# tricorder-photodiode-breakout-mk-1_0.net
KiCad netlist of a schematic drawn in EAGLE
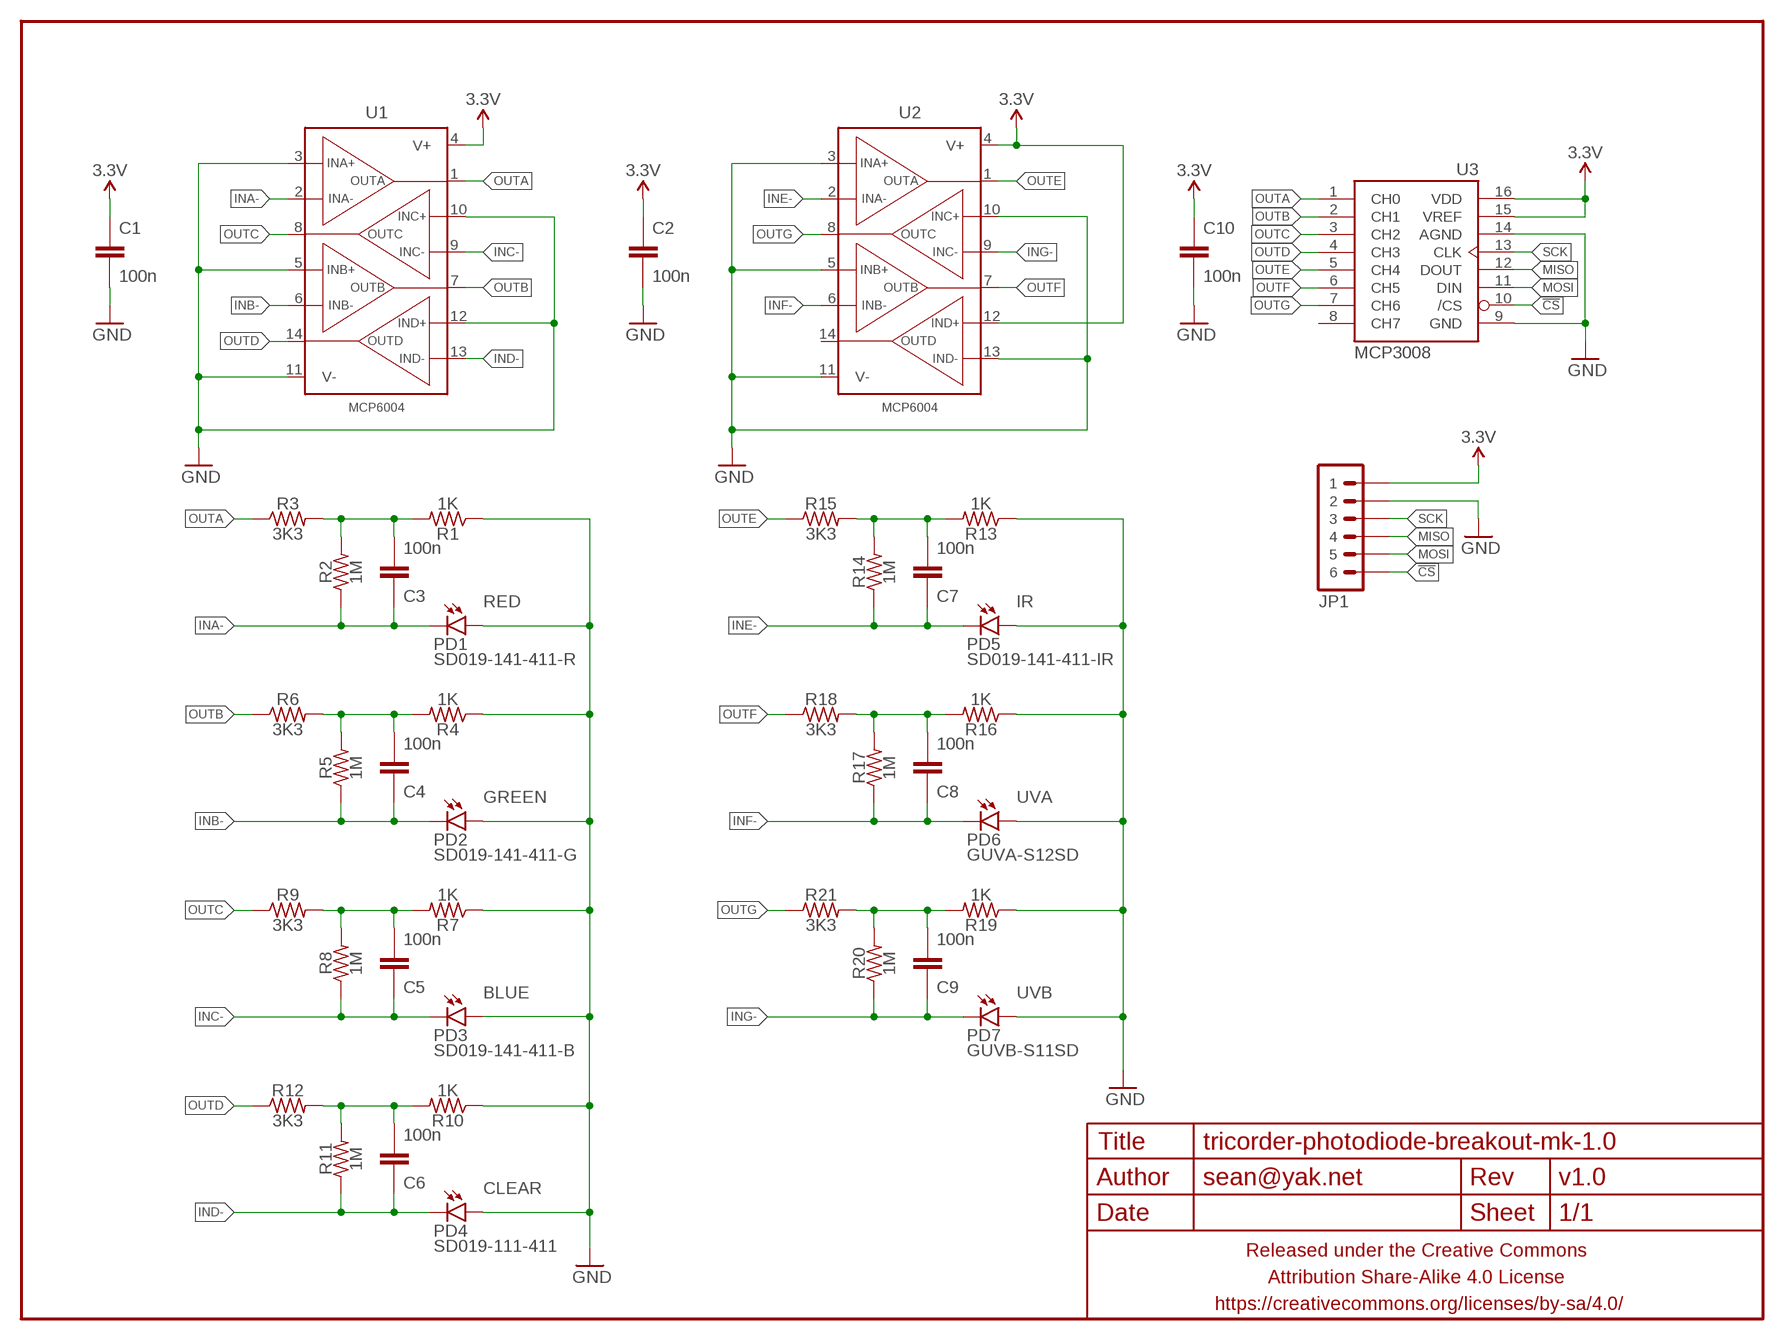
[diagram p0: schematic, sheet 1]

(export (version "E")
  (design (tool "Eeschema 10.0.6"))
  (components
    (comp (ref "C1")
      (value "100n")
      (footprint "eagle-import:C0603")
      (libsource (lib "eagle-import") (part "CAPACITOR-CERAMICC0603"))
    )
    (comp (ref "C2")
      (value "100n")
      (footprint "eagle-import:C0603")
      (libsource (lib "eagle-import") (part "CAPACITOR-CERAMICC0603"))
    )
    (comp (ref "C3")
      (value "100n")
      (footprint "eagle-import:C0603")
      (libsource (lib "eagle-import") (part "CAPACITOR-CERAMICC0603"))
    )
    (comp (ref "C4")
      (value "100n")
      (footprint "eagle-import:C0603")
      (libsource (lib "eagle-import") (part "CAPACITOR-CERAMICC0603"))
    )
    (comp (ref "C5")
      (value "100n")
      (footprint "eagle-import:C0603")
      (libsource (lib "eagle-import") (part "CAPACITOR-CERAMICC0603"))
    )
    (comp (ref "C6")
      (value "100n")
      (footprint "eagle-import:C0603")
      (libsource (lib "eagle-import") (part "CAPACITOR-CERAMICC0603"))
    )
    (comp (ref "C7")
      (value "100n")
      (footprint "eagle-import:C0603")
      (libsource (lib "eagle-import") (part "CAPACITOR-CERAMICC0603"))
    )
    (comp (ref "C8")
      (value "100n")
      (footprint "eagle-import:C0603")
      (libsource (lib "eagle-import") (part "CAPACITOR-CERAMICC0603"))
    )
    (comp (ref "C9")
      (value "100n")
      (footprint "eagle-import:C0603")
      (libsource (lib "eagle-import") (part "CAPACITOR-CERAMICC0603"))
    )
    (comp (ref "C10")
      (value "100n")
      (footprint "eagle-import:C0603")
      (libsource (lib "eagle-import") (part "CAPACITOR-CERAMICC0603"))
    )
    (comp (ref "FRAME1")
      (value "FRAME-LETTERNO_PACKAGE")
      (footprint "eagle-import:DUMMY")
      (fields (field (name "DESIGNER") "sean@yak.net") (field (name "VERSION") "v1.0"))
      (libsource (lib "eagle-import") (part "FRAME-LETTERNO_PACKAGE"))
    )
    (comp (ref "JP1")
      (value "M06JST-PH-PTH-VERT")
      (footprint "eagle-import:JST-6-PH-VERT-PTH")
      (libsource (lib "eagle-import") (part "M06JST-PH-PTH-VERT"))
    )
    (comp (ref "PD1")
      (value "SD019-141-411-R")
      (footprint "eagle-import:LED-0805")
      (libsource (lib "eagle-import") (part "PHOTODIODESMD-0805"))
    )
    (comp (ref "PD2")
      (value "SD019-141-411-G")
      (footprint "eagle-import:LED-0805")
      (libsource (lib "eagle-import") (part "PHOTODIODESMD-0805"))
    )
    (comp (ref "PD3")
      (value "SD019-141-411-B")
      (footprint "eagle-import:LED-0805")
      (libsource (lib "eagle-import") (part "PHOTODIODESMD-0805"))
    )
    (comp (ref "PD4")
      (value "SD019-111-411")
      (footprint "eagle-import:LED-0805")
      (libsource (lib "eagle-import") (part "PHOTODIODESMD-0805"))
    )
    (comp (ref "PD5")
      (value "SD019-141-411-IR")
      (footprint "eagle-import:LED-0805")
      (libsource (lib "eagle-import") (part "PHOTODIODESMD-0805"))
    )
    (comp (ref "PD6")
      (value "GUVA-S12SD")
      (footprint "eagle-import:LED3528")
      (libsource (lib "eagle-import") (part "PHOTODIODESMD-3528"))
    )
    (comp (ref "PD7")
      (value "GUVB-S11SD")
      (footprint "eagle-import:LED3528")
      (libsource (lib "eagle-import") (part "PHOTODIODESMD-3528"))
    )
    (comp (ref "R1")
      (value "1K")
      (footprint "eagle-import:R0603")
      (libsource (lib "eagle-import") (part "RESISTORR0603"))
    )
    (comp (ref "R2")
      (value "1M")
      (footprint "eagle-import:R0603")
      (libsource (lib "eagle-import") (part "RESISTORR0603"))
    )
    (comp (ref "R3")
      (value "3K3")
      (footprint "eagle-import:R0603")
      (libsource (lib "eagle-import") (part "RESISTORR0603"))
    )
    (comp (ref "R4")
      (value "1K")
      (footprint "eagle-import:R0603")
      (libsource (lib "eagle-import") (part "RESISTORR0603"))
    )
    (comp (ref "R5")
      (value "1M")
      (footprint "eagle-import:R0603")
      (libsource (lib "eagle-import") (part "RESISTORR0603"))
    )
    (comp (ref "R6")
      (value "3K3")
      (footprint "eagle-import:R0603")
      (libsource (lib "eagle-import") (part "RESISTORR0603"))
    )
    (comp (ref "R7")
      (value "1K")
      (footprint "eagle-import:R0603")
      (libsource (lib "eagle-import") (part "RESISTORR0603"))
    )
    (comp (ref "R8")
      (value "1M")
      (footprint "eagle-import:R0603")
      (libsource (lib "eagle-import") (part "RESISTORR0603"))
    )
    (comp (ref "R9")
      (value "3K3")
      (footprint "eagle-import:R0603")
      (libsource (lib "eagle-import") (part "RESISTORR0603"))
    )
    (comp (ref "R10")
      (value "1K")
      (footprint "eagle-import:R0603")
      (libsource (lib "eagle-import") (part "RESISTORR0603"))
    )
    (comp (ref "R11")
      (value "1M")
      (footprint "eagle-import:R0603")
      (libsource (lib "eagle-import") (part "RESISTORR0603"))
    )
    (comp (ref "R12")
      (value "3K3")
      (footprint "eagle-import:R0603")
      (libsource (lib "eagle-import") (part "RESISTORR0603"))
    )
    (comp (ref "R13")
      (value "1K")
      (footprint "eagle-import:R0603")
      (libsource (lib "eagle-import") (part "RESISTORR0603"))
    )
    (comp (ref "R14")
      (value "1M")
      (footprint "eagle-import:R0603")
      (libsource (lib "eagle-import") (part "RESISTORR0603"))
    )
    (comp (ref "R15")
      (value "3K3")
      (footprint "eagle-import:R0603")
      (libsource (lib "eagle-import") (part "RESISTORR0603"))
    )
    (comp (ref "R16")
      (value "1K")
      (footprint "eagle-import:R0603")
      (libsource (lib "eagle-import") (part "RESISTORR0603"))
    )
    (comp (ref "R17")
      (value "1M")
      (footprint "eagle-import:R0603")
      (libsource (lib "eagle-import") (part "RESISTORR0603"))
    )
    (comp (ref "R18")
      (value "3K3")
      (footprint "eagle-import:R0603")
      (libsource (lib "eagle-import") (part "RESISTORR0603"))
    )
    (comp (ref "R19")
      (value "1K")
      (footprint "eagle-import:R0603")
      (libsource (lib "eagle-import") (part "RESISTORR0603"))
    )
    (comp (ref "R20")
      (value "1M")
      (footprint "eagle-import:R0603")
      (libsource (lib "eagle-import") (part "RESISTORR0603"))
    )
    (comp (ref "R21")
      (value "3K3")
      (footprint "eagle-import:R0603")
      (libsource (lib "eagle-import") (part "RESISTORR0603"))
    )
    (comp (ref "U1")
      (value "MCP6004")
      (footprint "eagle-import:SO14")
      (libsource (lib "eagle-import") (part "MCP6004SOIC14"))
    )
    (comp (ref "U2")
      (value "MCP6004")
      (footprint "eagle-import:SO14")
      (libsource (lib "eagle-import") (part "MCP6004SOIC14"))
    )
    (comp (ref "U3")
      (value "MCP3008")
      (footprint "eagle-import:SO16")
      (libsource (lib "eagle-import") (part "MCP3008SOIC16"))
    )
  )
  (nets
    (net (code "1") (name "/~{CS}") (class "Default")
      (node (ref "JP1") (pin "6") (pinfunction "6_6") (pintype "passive"))
      (node (ref "U3") (pin "10") (pinfunction "/CS_10") (pintype "input"))
    )
    (net (code "2") (name "3.3V") (class "Default")
      (node (ref "C1") (pin "1") (pinfunction "1_1") (pintype "passive"))
      (node (ref "C10") (pin "1") (pinfunction "1_1") (pintype "passive"))
      (node (ref "C2") (pin "1") (pinfunction "1_1") (pintype "passive"))
      (node (ref "JP1") (pin "1") (pinfunction "1_1") (pintype "passive"))
      (node (ref "U1") (pin "4") (pinfunction "V+_4") (pintype "power_in"))
      (node (ref "U2") (pin "12") (pinfunction "IND+_12") (pintype "input"))
      (node (ref "U2") (pin "4") (pinfunction "V+_4") (pintype "power_in"))
      (node (ref "U3") (pin "15") (pinfunction "VREF_15") (pintype "input"))
      (node (ref "U3") (pin "16") (pinfunction "VDD_16") (pintype "power_in"))
    )
    (net (code "3") (name "GND") (class "Default")
      (node (ref "C1") (pin "2") (pinfunction "2_2") (pintype "passive"))
      (node (ref "C10") (pin "2") (pinfunction "2_2") (pintype "passive"))
      (node (ref "C2") (pin "2") (pinfunction "2_2") (pintype "passive"))
      (node (ref "JP1") (pin "2") (pinfunction "2_2") (pintype "passive"))
      (node (ref "PD1") (pin "A") (pinfunction "A_A") (pintype "passive"))
      (node (ref "PD2") (pin "A") (pinfunction "A_A") (pintype "passive"))
      (node (ref "PD3") (pin "A") (pinfunction "A_A") (pintype "passive"))
      (node (ref "PD4") (pin "A") (pinfunction "A_A") (pintype "passive"))
      (node (ref "PD5") (pin "A") (pinfunction "A_A") (pintype "passive"))
      (node (ref "PD6") (pin "A") (pinfunction "A_A") (pintype "passive"))
      (node (ref "PD7") (pin "A") (pinfunction "A_A") (pintype "passive"))
      (node (ref "R1") (pin "1") (pinfunction "1_1") (pintype "passive"))
      (node (ref "R10") (pin "1") (pinfunction "1_1") (pintype "passive"))
      (node (ref "R13") (pin "1") (pinfunction "1_1") (pintype "passive"))
      (node (ref "R16") (pin "1") (pinfunction "1_1") (pintype "passive"))
      (node (ref "R19") (pin "1") (pinfunction "1_1") (pintype "passive"))
      (node (ref "R4") (pin "1") (pinfunction "1_1") (pintype "passive"))
      (node (ref "R7") (pin "1") (pinfunction "1_1") (pintype "passive"))
      (node (ref "U1") (pin "10") (pinfunction "INC+_10") (pintype "input"))
      (node (ref "U1") (pin "11") (pinfunction "V-_11") (pintype "power_in"))
      (node (ref "U1") (pin "12") (pinfunction "IND+_12") (pintype "input"))
      (node (ref "U1") (pin "3") (pinfunction "INA+_3") (pintype "input"))
      (node (ref "U1") (pin "5") (pinfunction "INB+_5") (pintype "input"))
      (node (ref "U2") (pin "10") (pinfunction "INC+_10") (pintype "input"))
      (node (ref "U2") (pin "11") (pinfunction "V-_11") (pintype "power_in"))
      (node (ref "U2") (pin "13") (pinfunction "IND-_13") (pintype "input"))
      (node (ref "U2") (pin "3") (pinfunction "INA+_3") (pintype "input"))
      (node (ref "U2") (pin "5") (pinfunction "INB+_5") (pintype "input"))
      (node (ref "U3") (pin "14") (pinfunction "AGND_14") (pintype "power_in"))
      (node (ref "U3") (pin "9") (pinfunction "GND_9") (pintype "power_in"))
    )
    (net (code "4") (name "INA-") (class "Default")
      (node (ref "C3") (pin "1") (pinfunction "1_1") (pintype "passive"))
      (node (ref "PD1") (pin "C") (pinfunction "C_C") (pintype "passive"))
      (node (ref "R2") (pin "1") (pinfunction "1_1") (pintype "passive"))
      (node (ref "U1") (pin "2") (pinfunction "INA-_2") (pintype "input"))
    )
    (net (code "5") (name "INB-") (class "Default")
      (node (ref "C4") (pin "1") (pinfunction "1_1") (pintype "passive"))
      (node (ref "PD2") (pin "C") (pinfunction "C_C") (pintype "passive"))
      (node (ref "R5") (pin "1") (pinfunction "1_1") (pintype "passive"))
      (node (ref "U1") (pin "6") (pinfunction "INB-_6") (pintype "input"))
    )
    (net (code "6") (name "INC-") (class "Default")
      (node (ref "C5") (pin "1") (pinfunction "1_1") (pintype "passive"))
      (node (ref "PD3") (pin "C") (pinfunction "C_C") (pintype "passive"))
      (node (ref "R8") (pin "1") (pinfunction "1_1") (pintype "passive"))
      (node (ref "U1") (pin "9") (pinfunction "INC-_9") (pintype "input"))
    )
    (net (code "7") (name "IND-") (class "Default")
      (node (ref "C6") (pin "1") (pinfunction "1_1") (pintype "passive"))
      (node (ref "PD4") (pin "C") (pinfunction "C_C") (pintype "passive"))
      (node (ref "R11") (pin "1") (pinfunction "1_1") (pintype "passive"))
      (node (ref "U1") (pin "13") (pinfunction "IND-_13") (pintype "input"))
    )
    (net (code "8") (name "INE-") (class "Default")
      (node (ref "C7") (pin "1") (pinfunction "1_1") (pintype "passive"))
      (node (ref "PD5") (pin "C") (pinfunction "C_C") (pintype "passive"))
      (node (ref "R14") (pin "1") (pinfunction "1_1") (pintype "passive"))
      (node (ref "U2") (pin "2") (pinfunction "INA-_2") (pintype "input"))
    )
    (net (code "9") (name "INF-") (class "Default")
      (node (ref "C8") (pin "1") (pinfunction "1_1") (pintype "passive"))
      (node (ref "PD6") (pin "K") (pinfunction "C_K") (pintype "passive"))
      (node (ref "R17") (pin "1") (pinfunction "1_1") (pintype "passive"))
      (node (ref "U2") (pin "6") (pinfunction "INB-_6") (pintype "input"))
    )
    (net (code "10") (name "ING-") (class "Default")
      (node (ref "C9") (pin "1") (pinfunction "1_1") (pintype "passive"))
      (node (ref "PD7") (pin "K") (pinfunction "C_K") (pintype "passive"))
      (node (ref "R20") (pin "1") (pinfunction "1_1") (pintype "passive"))
      (node (ref "U2") (pin "9") (pinfunction "INC-_9") (pintype "input"))
    )
    (net (code "11") (name "MISO") (class "Default")
      (node (ref "JP1") (pin "4") (pinfunction "4_4") (pintype "passive"))
      (node (ref "U3") (pin "12") (pinfunction "DOUT_12") (pintype "output"))
    )
    (net (code "12") (name "MOSI") (class "Default")
      (node (ref "JP1") (pin "5") (pinfunction "5_5") (pintype "passive"))
      (node (ref "U3") (pin "11") (pinfunction "DIN_11") (pintype "input"))
    )
    (net (code "13") (name "Net-(C3-Pad2)") (class "Default")
      (node (ref "C3") (pin "2") (pinfunction "2_2") (pintype "passive"))
      (node (ref "R1") (pin "2") (pinfunction "2_2") (pintype "passive"))
      (node (ref "R2") (pin "2") (pinfunction "2_2") (pintype "passive"))
      (node (ref "R3") (pin "2") (pinfunction "2_2") (pintype "passive"))
    )
    (net (code "14") (name "Net-(C4-Pad2)") (class "Default")
      (node (ref "C4") (pin "2") (pinfunction "2_2") (pintype "passive"))
      (node (ref "R4") (pin "2") (pinfunction "2_2") (pintype "passive"))
      (node (ref "R5") (pin "2") (pinfunction "2_2") (pintype "passive"))
      (node (ref "R6") (pin "2") (pinfunction "2_2") (pintype "passive"))
    )
    (net (code "15") (name "Net-(C5-Pad2)") (class "Default")
      (node (ref "C5") (pin "2") (pinfunction "2_2") (pintype "passive"))
      (node (ref "R7") (pin "2") (pinfunction "2_2") (pintype "passive"))
      (node (ref "R8") (pin "2") (pinfunction "2_2") (pintype "passive"))
      (node (ref "R9") (pin "2") (pinfunction "2_2") (pintype "passive"))
    )
    (net (code "16") (name "Net-(C6-Pad2)") (class "Default")
      (node (ref "C6") (pin "2") (pinfunction "2_2") (pintype "passive"))
      (node (ref "R10") (pin "2") (pinfunction "2_2") (pintype "passive"))
      (node (ref "R11") (pin "2") (pinfunction "2_2") (pintype "passive"))
      (node (ref "R12") (pin "2") (pinfunction "2_2") (pintype "passive"))
    )
    (net (code "17") (name "Net-(C7-Pad2)") (class "Default")
      (node (ref "C7") (pin "2") (pinfunction "2_2") (pintype "passive"))
      (node (ref "R13") (pin "2") (pinfunction "2_2") (pintype "passive"))
      (node (ref "R14") (pin "2") (pinfunction "2_2") (pintype "passive"))
      (node (ref "R15") (pin "2") (pinfunction "2_2") (pintype "passive"))
    )
    (net (code "18") (name "Net-(C8-Pad2)") (class "Default")
      (node (ref "C8") (pin "2") (pinfunction "2_2") (pintype "passive"))
      (node (ref "R16") (pin "2") (pinfunction "2_2") (pintype "passive"))
      (node (ref "R17") (pin "2") (pinfunction "2_2") (pintype "passive"))
      (node (ref "R18") (pin "2") (pinfunction "2_2") (pintype "passive"))
    )
    (net (code "19") (name "Net-(C9-Pad2)") (class "Default")
      (node (ref "C9") (pin "2") (pinfunction "2_2") (pintype "passive"))
      (node (ref "R19") (pin "2") (pinfunction "2_2") (pintype "passive"))
      (node (ref "R20") (pin "2") (pinfunction "2_2") (pintype "passive"))
      (node (ref "R21") (pin "2") (pinfunction "2_2") (pintype "passive"))
    )
    (net (code "20") (name "OUTA") (class "Default")
      (node (ref "R3") (pin "1") (pinfunction "1_1") (pintype "passive"))
      (node (ref "U1") (pin "1") (pinfunction "OUTA_1") (pintype "output"))
      (node (ref "U3") (pin "1") (pinfunction "CH0_1") (pintype "input"))
    )
    (net (code "21") (name "OUTB") (class "Default")
      (node (ref "R6") (pin "1") (pinfunction "1_1") (pintype "passive"))
      (node (ref "U1") (pin "7") (pinfunction "OUTB_7") (pintype "output"))
      (node (ref "U3") (pin "2") (pinfunction "CH1_2") (pintype "input"))
    )
    (net (code "22") (name "OUTC") (class "Default")
      (node (ref "R9") (pin "1") (pinfunction "1_1") (pintype "passive"))
      (node (ref "U1") (pin "8") (pinfunction "OUTC_8") (pintype "output"))
      (node (ref "U3") (pin "3") (pinfunction "CH2_3") (pintype "input"))
    )
    (net (code "23") (name "OUTD") (class "Default")
      (node (ref "R12") (pin "1") (pinfunction "1_1") (pintype "passive"))
      (node (ref "U1") (pin "14") (pinfunction "OUTD_14") (pintype "output"))
      (node (ref "U3") (pin "4") (pinfunction "CH3_4") (pintype "input"))
    )
    (net (code "24") (name "OUTE") (class "Default")
      (node (ref "R15") (pin "1") (pinfunction "1_1") (pintype "passive"))
      (node (ref "U2") (pin "1") (pinfunction "OUTA_1") (pintype "output"))
      (node (ref "U3") (pin "5") (pinfunction "CH4_5") (pintype "input"))
    )
    (net (code "25") (name "OUTF") (class "Default")
      (node (ref "R18") (pin "1") (pinfunction "1_1") (pintype "passive"))
      (node (ref "U2") (pin "7") (pinfunction "OUTB_7") (pintype "output"))
      (node (ref "U3") (pin "6") (pinfunction "CH5_6") (pintype "input"))
    )
    (net (code "26") (name "OUTG") (class "Default")
      (node (ref "R21") (pin "1") (pinfunction "1_1") (pintype "passive"))
      (node (ref "U2") (pin "8") (pinfunction "OUTC_8") (pintype "output"))
      (node (ref "U3") (pin "7") (pinfunction "CH6_7") (pintype "input"))
    )
    (net (code "27") (name "SCK") (class "Default")
      (node (ref "JP1") (pin "3") (pinfunction "3_3") (pintype "passive"))
      (node (ref "U3") (pin "13") (pinfunction "CLK_13") (pintype "input"))
    )
    (net (code "28") (name "unconnected-(U2-OUTD-Pad14)") (class "Default")
      (node (ref "U2") (pin "14") (pinfunction "OUTD_14") (pintype "output"))
    )
    (net (code "29") (name "unconnected-(U3-CH7-Pad8)") (class "Default")
      (node (ref "U3") (pin "8") (pinfunction "CH7_8") (pintype "input"))
    )
  )
)
